# SheetV7_2.net
KiCad netlist of a schematic drawn in Altium Designer
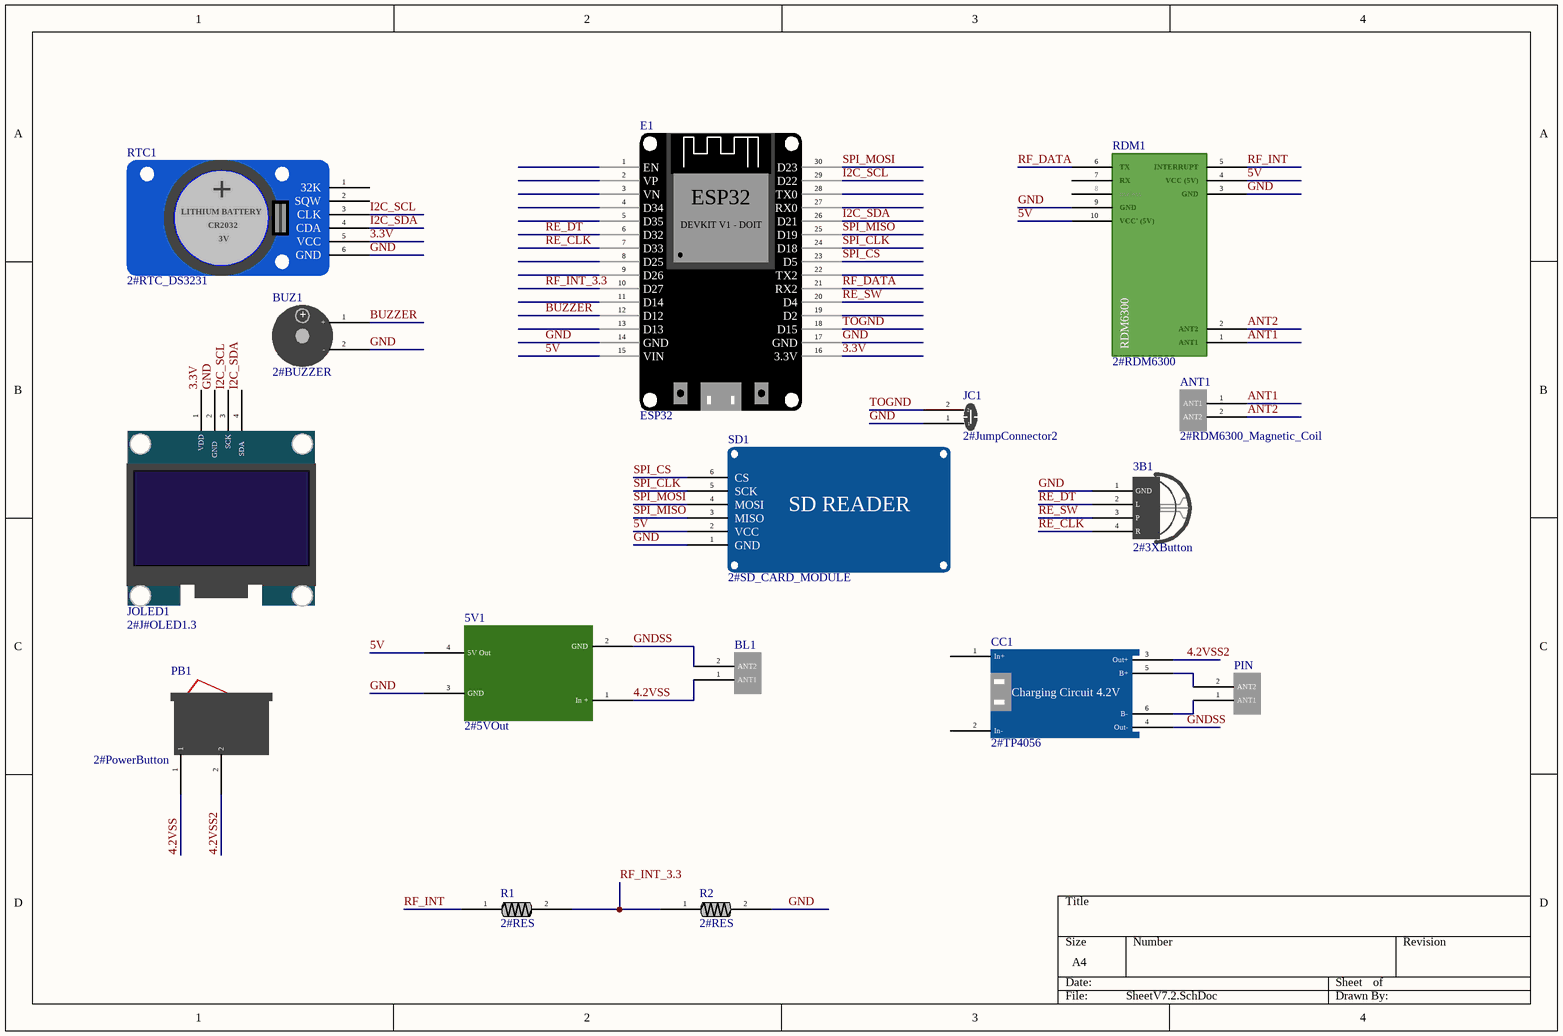
[diagram p0: SheetV7.2.SchDoc]

(export (version "E")
  (design (tool "Eeschema 10.0.6"))
  (components
    (comp (ref "3B1")
      (value "2#3XButton")
      (footprint "2#3XButton")
      (libsource (lib "Sch") (part "2#3XButton"))
    )
    (comp (ref "5V1") (value "2#5VOut") (footprint "2#5VOut") (libsource (lib "Sch") (part "2#5VOut")))
    (comp (ref "ANT1")
      (value "2#RDM6300_Magnetic_Coil")
      (footprint "2#RDM6300_Magnetic_Coil")
      (libsource (lib "") (part "2#RDM6300_Magnetic_Coil_1"))
    )
    (comp (ref "BL1")
      (value "2#RDM6300_Magnetic_Coil")
      (footprint "2#RDM6300_Magnetic_Coil")
      (libsource (lib "Sch") (part "2#RDM6300_Magnetic_Coil"))
    )
    (comp (ref "BUZ1") (value "2#BUZZER") (footprint "2#BUZZER") (libsource (lib "Sch") (part "2#BUZZER")))
    (comp (ref "CC1") (value "2#TP4056") (footprint "2#TP4056") (libsource (lib "Sch") (part "2#TP4056")))
    (comp (ref "E1")
      (value "ESP32")
      (footprint "2#1.5mmHole#ESP32")
      (libsource (lib "Sch") (part "2#B#ESP32_DOIT_DEVKIT_V1"))
    )
    (comp (ref "JC1")
      (value "2#JumpConnector2")
      (footprint "2#JumpConnector2")
      (libsource (lib "Sch") (part "2#JumpConnector2"))
    )
    (comp (ref "JOLED1")
      (value "2#J#OLED1.3")
      (footprint "2#Jump4#OLED_1.3")
      (libsource (lib "Sch") (part "2#J#OLED1.3"))
    )
    (comp (ref "PB1")
      (value "2#PowerButton")
      (footprint "2#PowerButton")
      (libsource (lib "Sch") (part "2#PowerButton"))
    )
    (comp (ref "PIN")
      (value "2#RDM6300_Magnetic_Coil")
      (footprint "2#RDM6300_Magnetic_Coil")
      (libsource (lib "Sch") (part "2#RDM6300_Magnetic_Coil"))
    )
    (comp (ref "R1") (value "2#RES") (footprint "2#RES") (libsource (lib "Sch") (part "2#RES")))
    (comp (ref "R2") (value "2#RES") (footprint "2#RES") (libsource (lib "Sch") (part "2#RES")))
    (comp (ref "RDM1") (value "2#RDM6300") (footprint "2#RDM6300") (libsource (lib "Sch") (part "2#RDM6300")))
    (comp (ref "RTC1")
      (value "2#RTC_DS3231")
      (footprint "2#RTC_DS3231")
      (libsource (lib "Sch") (part "2#RTC_DS3231"))
    )
    (comp (ref "SD1")
      (value "2#SD_CARD_MODULE")
      (footprint "2#SD_READER")
      (libsource (lib "Sch") (part "2#SD_CARD_MODULE"))
    )
  )
  (nets
    (net (code "1") (name "/3.3V") (class "Default")
      (node (ref "E1") (pin "16") (pinfunction "3.3V_16") (pintype "passive"))
      (node (ref "JOLED1") (pin "1") (pinfunction "VDD_1") (pintype "passive"))
      (node (ref "RTC1") (pin "5") (pinfunction "VCC_5") (pintype "passive"))
    )
    (net (code "2") (name "/4.2VSS") (class "Default")
      (node (ref "5V1") (pin "1") (pinfunction "In_+_1") (pintype "passive"))
      (node (ref "BL1") (pin "1") (pinfunction "ANT1_1") (pintype "passive"))
      (node (ref "PB1") (pin "1") (pinfunction "1_1") (pintype "passive"))
    )
    (net (code "3") (name "/4.2VSS2") (class "Default")
      (node (ref "CC1") (pin "3") (pinfunction "Out+_3") (pintype "passive"))
      (node (ref "PB1") (pin "2") (pinfunction "2_2") (pintype "passive"))
    )
    (net (code "4") (name "/5V") (class "Default")
      (node (ref "5V1") (pin "4") (pinfunction "5V_Out_4") (pintype "passive"))
      (node (ref "E1") (pin "15") (pinfunction "VIN_15") (pintype "passive"))
      (node (ref "RDM1") (pin "10") (pinfunction "VCC'_(5V)_10") (pintype "passive"))
      (node (ref "RDM1") (pin "4") (pinfunction "VCC_(5V)_4") (pintype "power_in"))
      (node (ref "SD1") (pin "2") (pinfunction "VCC_2") (pintype "passive"))
    )
    (net (code "5") (name "/ANT1") (class "Default")
      (node (ref "ANT1") (pin "1") (pinfunction "ANT1_1") (pintype "passive"))
      (node (ref "RDM1") (pin "1") (pinfunction "ANT1_1") (pintype "power_in"))
    )
    (net (code "6") (name "/ANT2") (class "Default")
      (node (ref "ANT1") (pin "2") (pinfunction "ANT2_2") (pintype "passive"))
      (node (ref "RDM1") (pin "2") (pinfunction "ANT2_2") (pintype "passive"))
    )
    (net (code "7") (name "/BUZZER") (class "Default")
      (node (ref "BUZ1") (pin "1") (pinfunction "+_1") (pintype "passive"))
      (node (ref "E1") (pin "12") (pinfunction "D12_12") (pintype "passive"))
    )
    (net (code "8") (name "/GND") (class "Default")
      (node (ref "3B1") (pin "1") (pinfunction "GND_1") (pintype "passive"))
      (node (ref "5V1") (pin "3") (pinfunction "GND_3") (pintype "passive"))
      (node (ref "BUZ1") (pin "2") (pinfunction "-_2") (pintype "passive"))
      (node (ref "E1") (pin "14") (pinfunction "GND_14") (pintype "passive"))
      (node (ref "E1") (pin "17") (pinfunction "GND_17") (pintype "passive"))
      (node (ref "JC1") (pin "1") (pinfunction "1_1") (pintype "passive"))
      (node (ref "JOLED1") (pin "2") (pinfunction "GND_2") (pintype "passive"))
      (node (ref "R2") (pin "2") (pinfunction "2_2") (pintype "passive"))
      (node (ref "RDM1") (pin "3") (pinfunction "GND_3") (pintype "passive"))
      (node (ref "RDM1") (pin "9") (pinfunction "GND_9") (pintype "passive"))
      (node (ref "RTC1") (pin "6") (pinfunction "GND_6") (pintype "passive"))
      (node (ref "SD1") (pin "1") (pinfunction "GND_1") (pintype "passive"))
    )
    (net (code "9") (name "/GNDSS") (class "Default")
      (node (ref "5V1") (pin "2") (pinfunction "GND_2") (pintype "passive"))
      (node (ref "BL1") (pin "2") (pinfunction "ANT2_2") (pintype "passive"))
      (node (ref "CC1") (pin "4") (pinfunction "Out-_4") (pintype "passive"))
    )
    (net (code "10") (name "/I2C_SCL") (class "Default")
      (node (ref "E1") (pin "29") (pinfunction "D22_29") (pintype "passive"))
      (node (ref "JOLED1") (pin "3") (pinfunction "SCK_3") (pintype "passive"))
      (node (ref "RTC1") (pin "3") (pinfunction "CLK_3") (pintype "passive"))
    )
    (net (code "11") (name "/I2C_SDA") (class "Default")
      (node (ref "E1") (pin "26") (pinfunction "D21_26") (pintype "passive"))
      (node (ref "JOLED1") (pin "4") (pinfunction "SDA_4") (pintype "passive"))
      (node (ref "RTC1") (pin "4") (pinfunction "CDA_4") (pintype "passive"))
    )
    (net (code "12") (name "/RE_CLK") (class "Default")
      (node (ref "3B1") (pin "4") (pinfunction "R_4") (pintype "passive"))
      (node (ref "E1") (pin "7") (pinfunction "D33_7") (pintype "passive"))
    )
    (net (code "13") (name "/RE_DT") (class "Default")
      (node (ref "3B1") (pin "2") (pinfunction "L_2") (pintype "passive"))
      (node (ref "E1") (pin "6") (pinfunction "D32_6") (pintype "passive"))
    )
    (net (code "14") (name "/RE_SW") (class "Default")
      (node (ref "3B1") (pin "3") (pinfunction "P_3") (pintype "passive"))
      (node (ref "E1") (pin "20") (pinfunction "D4_20") (pintype "passive"))
    )
    (net (code "15") (name "/RF_DATA") (class "Default")
      (node (ref "E1") (pin "21") (pinfunction "RX2_21") (pintype "passive"))
      (node (ref "RDM1") (pin "6") (pinfunction "TX_6") (pintype "passive"))
    )
    (net (code "16") (name "/RF_INT") (class "Default")
      (node (ref "R1") (pin "1") (pinfunction "1_1") (pintype "passive"))
      (node (ref "RDM1") (pin "5") (pinfunction "INTERRUPT_5") (pintype "passive"))
    )
    (net (code "17") (name "/RF_INT_3.3") (class "Default")
      (node (ref "E1") (pin "10") (pinfunction "D27_10") (pintype "passive"))
      (node (ref "R1") (pin "2") (pinfunction "2_2") (pintype "passive"))
      (node (ref "R2") (pin "1") (pinfunction "1_1") (pintype "passive"))
    )
    (net (code "18") (name "/SPI_CLK") (class "Default")
      (node (ref "E1") (pin "24") (pinfunction "D18_24") (pintype "passive"))
      (node (ref "SD1") (pin "5") (pinfunction "SCK_5") (pintype "passive"))
    )
    (net (code "19") (name "/SPI_CS") (class "Default")
      (node (ref "E1") (pin "23") (pinfunction "D5_23") (pintype "passive"))
      (node (ref "SD1") (pin "6") (pinfunction "CS_6") (pintype "passive"))
    )
    (net (code "20") (name "/SPI_MISO") (class "Default")
      (node (ref "E1") (pin "25") (pinfunction "D19_25") (pintype "passive"))
      (node (ref "SD1") (pin "3") (pinfunction "MISO_3") (pintype "passive"))
    )
    (net (code "21") (name "/SPI_MOSI") (class "Default")
      (node (ref "E1") (pin "30") (pinfunction "D23_30") (pintype "passive"))
      (node (ref "SD1") (pin "4") (pinfunction "MOSI_4") (pintype "passive"))
    )
    (net (code "22") (name "/TOGND") (class "Default")
      (node (ref "E1") (pin "18") (pinfunction "D15_18") (pintype "passive"))
      (node (ref "JC1") (pin "2") (pinfunction "2_2") (pintype "passive"))
    )
    (net (code "23") (name "Net-(CC1-B+)") (class "Default")
      (node (ref "CC1") (pin "5") (pinfunction "B+_5") (pintype "passive"))
      (node (ref "PIN") (pin "2") (pinfunction "ANT2_2") (pintype "passive"))
    )
    (net (code "24") (name "Net-(CC1-B-)") (class "Default")
      (node (ref "CC1") (pin "6") (pinfunction "B-_6") (pintype "passive"))
      (node (ref "PIN") (pin "1") (pinfunction "ANT1_1") (pintype "passive"))
    )
    (net (code "25") (name "unconnected-(CC1-In+-Pad1)") (class "Default")
      (node (ref "CC1") (pin "1") (pinfunction "In+_1") (pintype "passive"))
    )
    (net (code "26") (name "unconnected-(CC1-In--Pad2)") (class "Default")
      (node (ref "CC1") (pin "2") (pinfunction "In-_2") (pintype "passive"))
    )
    (net (code "27") (name "unconnected-(E1-D2-Pad19)") (class "Default")
      (node (ref "E1") (pin "19") (pinfunction "D2_19") (pintype "passive"))
    )
    (net (code "28") (name "unconnected-(E1-D13-Pad13)") (class "Default")
      (node (ref "E1") (pin "13") (pinfunction "D13_13") (pintype "passive"))
    )
    (net (code "29") (name "unconnected-(E1-D14-Pad11)") (class "Default")
      (node (ref "E1") (pin "11") (pinfunction "D14_11") (pintype "passive"))
    )
    (net (code "30") (name "unconnected-(E1-D25-Pad8)") (class "Default")
      (node (ref "E1") (pin "8") (pinfunction "D25_8") (pintype "passive"))
    )
    (net (code "31") (name "unconnected-(E1-D26-Pad9)") (class "Default")
      (node (ref "E1") (pin "9") (pinfunction "D26_9") (pintype "passive"))
    )
    (net (code "32") (name "unconnected-(E1-D34-Pad4)") (class "Default")
      (node (ref "E1") (pin "4") (pinfunction "D34_4") (pintype "passive"))
    )
    (net (code "33") (name "unconnected-(E1-D35-Pad5)") (class "Default")
      (node (ref "E1") (pin "5") (pinfunction "D35_5") (pintype "passive"))
    )
    (net (code "34") (name "unconnected-(E1-EN-Pad1)") (class "Default")
      (node (ref "E1") (pin "1") (pinfunction "EN_1") (pintype "passive"))
    )
    (net (code "35") (name "unconnected-(E1-RX0-Pad27)") (class "Default")
      (node (ref "E1") (pin "27") (pinfunction "RX0_27") (pintype "passive"))
    )
    (net (code "36") (name "unconnected-(E1-TX0-Pad28)") (class "Default")
      (node (ref "E1") (pin "28") (pinfunction "TX0_28") (pintype "passive"))
    )
    (net (code "37") (name "unconnected-(E1-TX2-Pad22)") (class "Default")
      (node (ref "E1") (pin "22") (pinfunction "TX2_22") (pintype "passive"))
    )
    (net (code "38") (name "unconnected-(E1-VN-Pad3)") (class "Default")
      (node (ref "E1") (pin "3") (pinfunction "VN_3") (pintype "passive"))
    )
    (net (code "39") (name "unconnected-(E1-VP-Pad2)") (class "Default")
      (node (ref "E1") (pin "2") (pinfunction "VP_2") (pintype "passive"))
    )
    (net (code "40") (name "unconnected-(RDM1-RX-Pad7)") (class "Default")
      (node (ref "RDM1") (pin "7") (pinfunction "RX_7") (pintype "passive"))
    )
    (net (code "41") (name "unconnected-(RDM1-useless-Pad8)") (class "Default")
      (node (ref "RDM1") (pin "8") (pinfunction "useless_8") (pintype "passive"))
    )
    (net (code "42") (name "unconnected-(RTC1-32K-Pad1)") (class "Default")
      (node (ref "RTC1") (pin "1") (pinfunction "32K_1") (pintype "passive"))
    )
    (net (code "43") (name "unconnected-(RTC1-SQW-Pad2)") (class "Default")
      (node (ref "RTC1") (pin "2") (pinfunction "SQW_2") (pintype "passive"))
    )
  )
)
